# sFMC98_v2.net
KiCad netlist of a schematic drawn in Altium Designer
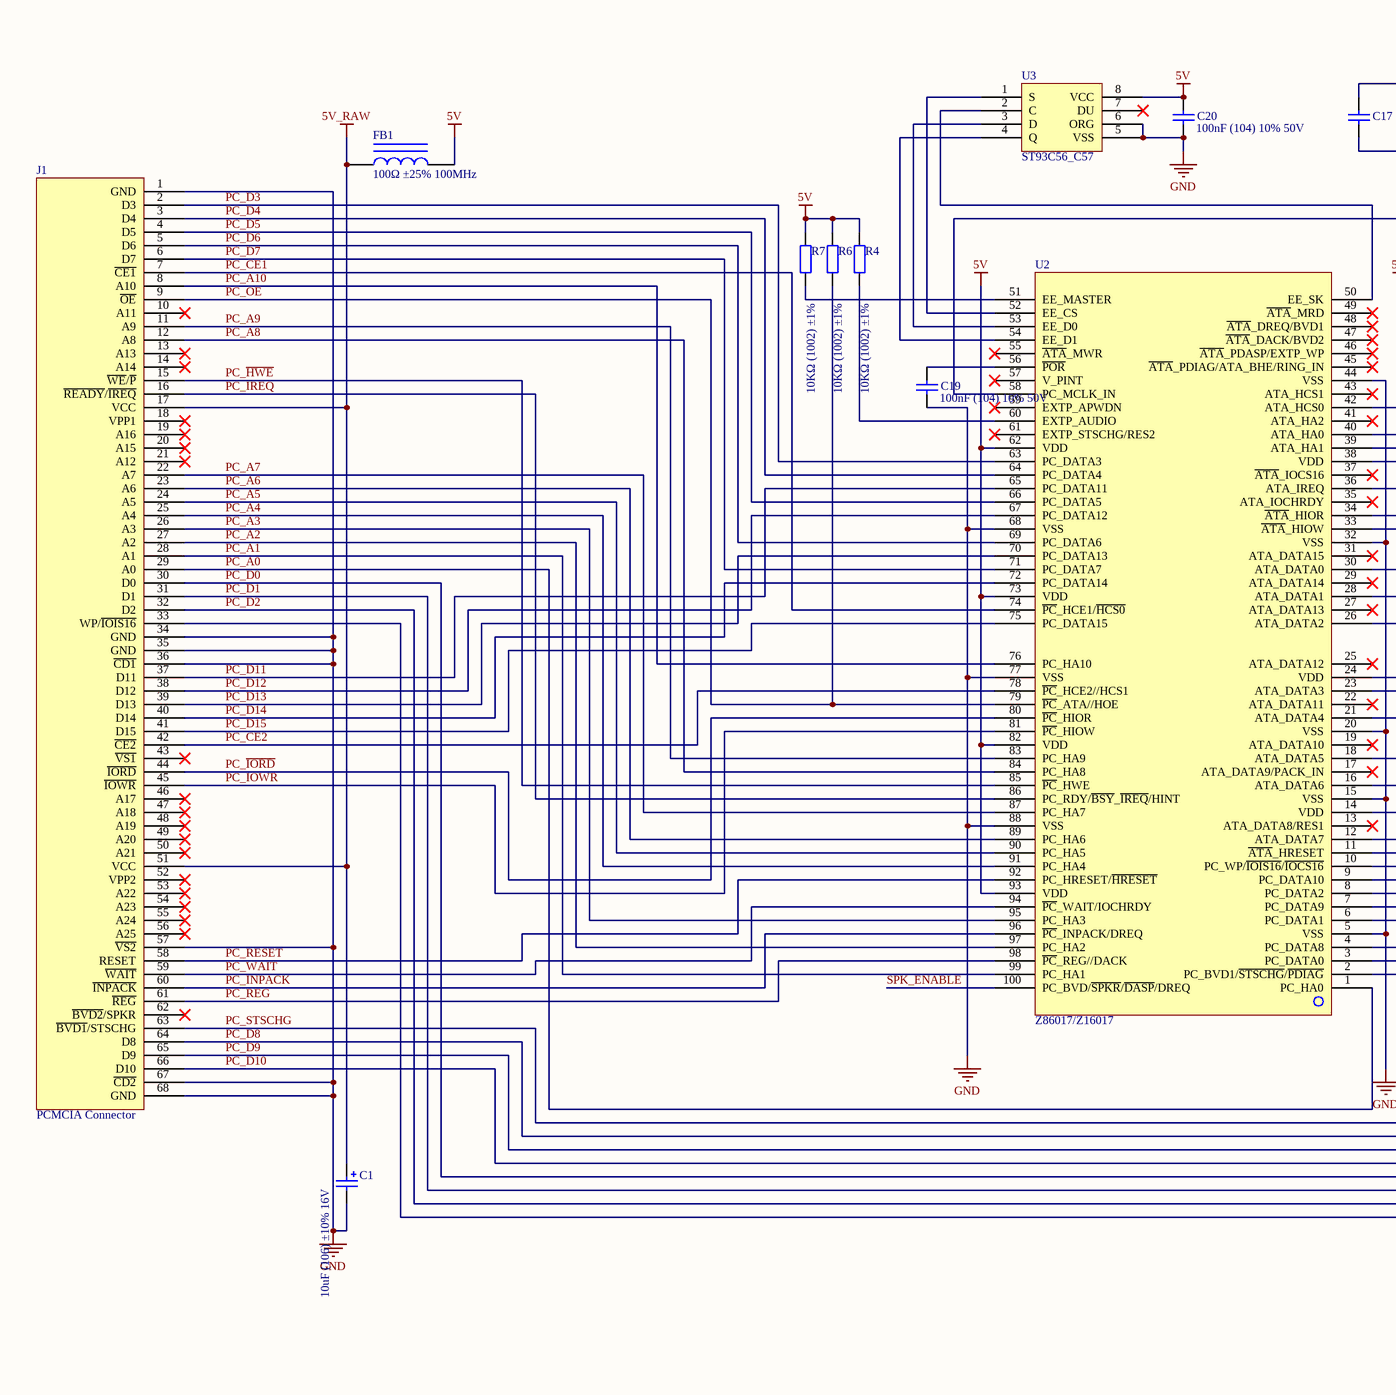
[diagram p0: sFMC98_v2.SchDoc, left]
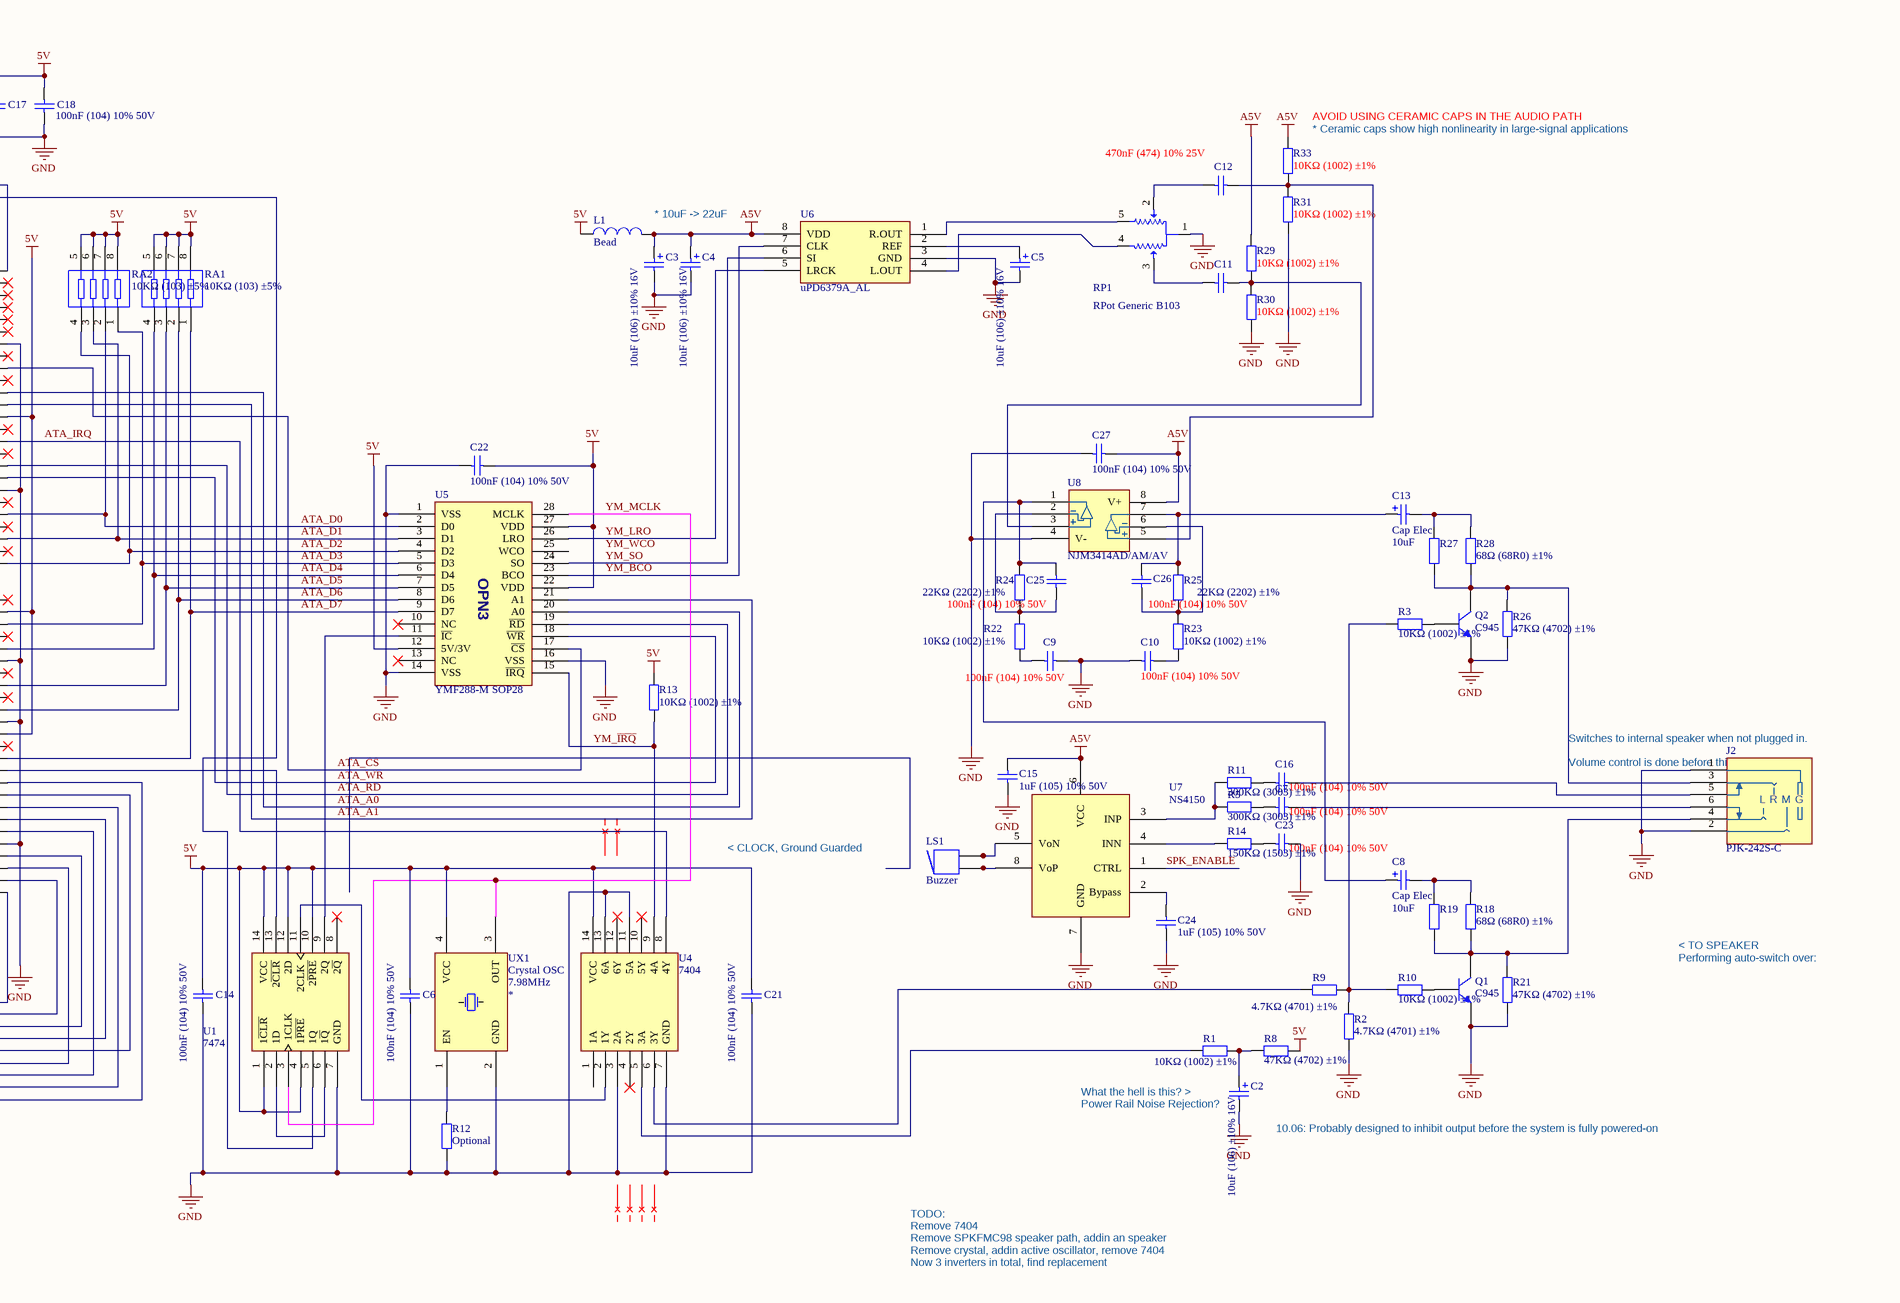
[diagram p1: sFMC98_v2.SchDoc, right]

(export (version "E")
  (design (tool "Eeschema 10.0.6"))
  (components
    (comp (ref "C1")
      (value "10uF (106) ±10% 16V")
      (footprint "CASE-A_3216")
      (description "钽电容")
      (libsource (lib "JLC_Cap") (part "3216 10uF (106) 10% 16V"))
    )
    (comp (ref "C2")
      (value "10uF (106) ±10% 16V")
      (footprint "CASE-A_3216")
      (description "钽电容")
      (libsource (lib "JLC_Cap") (part "3216 10uF (106) 10% 16V"))
    )
    (comp (ref "C3")
      (value "10uF (106) ±10% 16V")
      (footprint "CASE-A_3216")
      (description "钽电容")
      (libsource (lib "JLC_Cap") (part "3216 10uF (106) 10% 16V"))
    )
    (comp (ref "C4")
      (value "10uF (106) ±10% 16V")
      (footprint "CASE-A_3216")
      (description "钽电容")
      (libsource (lib "JLC_Cap") (part "3216 10uF (106) 10% 16V"))
    )
    (comp (ref "C5")
      (value "10uF (106) ±10% 16V")
      (footprint "CASE-A_3216")
      (description "钽电容")
      (libsource (lib "JLC_Cap") (part "3216 10uF (106) 10% 16V"))
    )
    (comp (ref "C6")
      (value "100nF (104) 10% 50V")
      (footprint "0603_C")
      (description "贴片电容")
      (libsource (lib "JLC_Cap") (part "0603 100nF (104) 10% 50V"))
    )
    (comp (ref "C7")
      (value "100nF (104) 10% 50V")
      (footprint "0603_C")
      (description "贴片电容")
      (libsource (lib "JLC_Cap") (part "0603 100nF (104) 10% 50V"))
    )
    (comp (ref "C8")
      (value "Cap Elec")
      (footprint "C-RB-4_5MM_Cutout")
      (description "Polarized Capacitor (Surface Mount)")
      (fields (field (name "ALTIUM_VALUE") "10uF") (field (name "PUBLISHER") "Altium Limited"))
      (libsource (lib "DiscreteRF") (part "Cap Pol3"))
    )
    (comp (ref "C9")
      (value "100nF (104) 10% 50V")
      (footprint "0603_C")
      (description "贴片电容")
      (libsource (lib "JLC_Cap") (part "0603 100nF (104) 10% 50V"))
    )
    (comp (ref "C10")
      (value "100nF (104) 10% 50V")
      (footprint "0603_C")
      (description "贴片电容")
      (libsource (lib "JLC_Cap") (part "0603 100nF (104) 10% 50V"))
    )
    (comp (ref "C11")
      (value "470nF (474) 10% 25V")
      (footprint "0603_C")
      (description "贴片电容")
      (libsource (lib "JLC_Cap") (part "0603 470nF (474) 10% 25V"))
    )
    (comp (ref "C12")
      (value "470nF (474) 10% 25V")
      (footprint "0603_C")
      (description "贴片电容")
      (libsource (lib "JLC_Cap") (part "0603 470nF (474) 10% 25V"))
    )
    (comp (ref "C13")
      (value "Cap Elec")
      (footprint "C-RB-4_5MM_Cutout")
      (description "Polarized Capacitor (Surface Mount)")
      (fields (field (name "ALTIUM_VALUE") "10uF") (field (name "PUBLISHER") "Altium Limited"))
      (libsource (lib "DiscreteRF") (part "Cap Pol3"))
    )
    (comp (ref "C14")
      (value "100nF (104) 10% 50V")
      (footprint "0603_C")
      (description "贴片电容")
      (libsource (lib "JLC_Cap") (part "0603 100nF (104) 10% 50V"))
    )
    (comp (ref "C15")
      (value "1uF (105) 10% 50V")
      (footprint "0603_C")
      (description "贴片电容")
      (libsource (lib "JLC_Cap") (part "0603 1uF (105) 10% 50V"))
    )
    (comp (ref "C16")
      (value "100nF (104) 10% 50V")
      (footprint "0603_C")
      (description "贴片电容")
      (libsource (lib "JLC_Cap") (part "0603 100nF (104) 10% 50V"))
    )
    (comp (ref "C17")
      (value "100nF (104) 10% 50V")
      (footprint "0603_C")
      (description "贴片电容")
      (libsource (lib "JLC_Cap") (part "0603 100nF (104) 10% 50V"))
    )
    (comp (ref "C18")
      (value "100nF (104) 10% 50V")
      (footprint "0603_C")
      (description "贴片电容")
      (libsource (lib "JLC_Cap") (part "0603 100nF (104) 10% 50V"))
    )
    (comp (ref "C19")
      (value "100nF (104) 10% 50V")
      (footprint "0603_C")
      (description "贴片电容")
      (libsource (lib "JLC_Cap") (part "0603 100nF (104) 10% 50V"))
    )
    (comp (ref "C20")
      (value "100nF (104) 10% 50V")
      (footprint "0603_C")
      (description "贴片电容")
      (libsource (lib "JLC_Cap") (part "0603 100nF (104) 10% 50V"))
    )
    (comp (ref "C21")
      (value "100nF (104) 10% 50V")
      (footprint "0603_C")
      (description "贴片电容")
      (libsource (lib "JLC_Cap") (part "0603 100nF (104) 10% 50V"))
    )
    (comp (ref "C22")
      (value "100nF (104) 10% 50V")
      (footprint "0603_C")
      (description "贴片电容")
      (libsource (lib "JLC_Cap") (part "0603 100nF (104) 10% 50V"))
    )
    (comp (ref "C23")
      (value "100nF (104) 10% 50V")
      (footprint "0603_C")
      (description "贴片电容")
      (libsource (lib "JLC_Cap") (part "0603 100nF (104) 10% 50V"))
    )
    (comp (ref "C24")
      (value "1uF (105) 10% 50V")
      (footprint "0603_C")
      (description "贴片电容")
      (libsource (lib "JLC_Cap") (part "0603 1uF (105) 10% 50V"))
    )
    (comp (ref "C25")
      (value "100nF (104) 10% 50V")
      (footprint "0603_C")
      (description "贴片电容")
      (libsource (lib "JLC_Cap") (part "0603 100nF (104) 10% 50V"))
    )
    (comp (ref "C26")
      (value "100nF (104) 10% 50V")
      (footprint "0603_C")
      (description "贴片电容")
      (libsource (lib "JLC_Cap") (part "0603 100nF (104) 10% 50V"))
    )
    (comp (ref "C27")
      (value "100nF (104) 10% 50V")
      (footprint "0603_C")
      (description "贴片电容")
      (libsource (lib "JLC_Cap") (part "0603 100nF (104) 10% 50V"))
    )
    (comp (ref "FB1")
      (value "100Ω ±25% 100MHz")
      (footprint "0805_L")
      (description "贴片磁珠")
      (libsource (lib "JLC_IUD") (part "0805 100Ω 25% 100MHz"))
    )
    (comp (ref "J1")
      (value "PCMCIA Connector")
      (footprint "PCF-SMT-K1")
      (libsource (lib "PrimaryLIB1") (part "PCMCIA_Conn"))
    )
    (comp (ref "J2")
      (value "PJK-242S-C")
      (footprint "PJK-242S-C")
      (description "2.5mm Headphone Jack")
      (libsource (lib "PrimaryLIB1") (part "PJK-242S-C"))
    )
    (comp (ref "L1")
      (value "Bead")
      (footprint "L2012X10N_LQW21")
      (description "Inductor")
      (fields (field (name "PUBLISHER") "Altium Limited"))
      (libsource (lib "DiscreteRF") (part "Inductor"))
    )
    (comp (ref "LS1")
      (value "Buzzer")
      (footprint "SPK_PCB_MOUNT")
      (description "Magnetic Transducer Buzzer")
      (fields (field (name "PUBLISHER") "Altium Limited"))
      (libsource (lib "Miscellaneous Devices") (part "Buzzer"))
    )
    (comp (ref "Q1")
      (value "C945")
      (footprint "SOT-23(SOT-23-3)")
      (description "三极管")
      (libsource (lib "JLC_Transistor_NPN") (part "SOT-23 SS8050 Y1"))
    )
    (comp (ref "Q2")
      (value "C945")
      (footprint "SOT-23(SOT-23-3)")
      (description "三极管")
      (libsource (lib "JLC_Transistor_NPN") (part "SOT-23 SS8050 Y1"))
    )
    (comp (ref "R1")
      (value "10KΩ (1002) ±1%")
      (footprint "0603_R")
      (description "贴片电阻")
      (libsource (lib "") (part "0603 10KΩ (1002) 1%_1"))
    )
    (comp (ref "R2")
      (value "4.7KΩ (4701) ±1%")
      (footprint "0603_R")
      (description "贴片电阻")
      (libsource (lib "") (part "0603 4.7KΩ (4701) 1%_1"))
    )
    (comp (ref "R3")
      (value "10KΩ (1002) ±1%")
      (footprint "0603_R")
      (description "贴片电阻")
      (libsource (lib "") (part "0603 10KΩ (1002) 1%_1"))
    )
    (comp (ref "R4")
      (value "10KΩ (1002) ±1%")
      (footprint "0603_R")
      (description "贴片电阻")
      (libsource (lib "JLC_RES") (part "0603 10KΩ (1002) 1%"))
    )
    (comp (ref "R5")
      (value "300KΩ (3003) ±1%")
      (footprint "0603_R")
      (description "贴片电阻")
      (libsource (lib "JLC_RES") (part "0603 300KΩ (3003) 1%"))
    )
    (comp (ref "R6")
      (value "10KΩ (1002) ±1%")
      (footprint "0603_R")
      (description "贴片电阻")
      (libsource (lib "JLC_RES") (part "0603 10KΩ (1002) 1%"))
    )
    (comp (ref "R7")
      (value "10KΩ (1002) ±1%")
      (footprint "0603_R")
      (description "贴片电阻")
      (libsource (lib "JLC_RES") (part "0603 10KΩ (1002) 1%"))
    )
    (comp (ref "R8")
      (value "47KΩ (4702) ±1%")
      (footprint "0603_R")
      (description "贴片电阻")
      (libsource (lib "") (part "0603 47KΩ (4702) 1%_1"))
    )
    (comp (ref "R9")
      (value "4.7KΩ (4701) ±1%")
      (footprint "0603_R")
      (description "贴片电阻")
      (libsource (lib "JLC_RES") (part "0603 4.7KΩ (4701) 1%"))
    )
    (comp (ref "R10")
      (value "10KΩ (1002) ±1%")
      (footprint "0603_R")
      (description "贴片电阻")
      (libsource (lib "") (part "0603 10KΩ (1002) 1%_1"))
    )
    (comp (ref "R11")
      (value "300KΩ (3003) ±1%")
      (footprint "0603_R")
      (description "贴片电阻")
      (libsource (lib "JLC_RES") (part "0603 300KΩ (3003) 1%"))
    )
    (comp (ref "R12")
      (value "Optional")
      (footprint "0603_R")
      (description "贴片电阻")
      (libsource (lib "JLC_RES") (part "0603 10KΩ (1002) 1%"))
    )
    (comp (ref "R13")
      (value "10KΩ (1002) ±1%")
      (footprint "0603_R")
      (description "贴片电阻")
      (libsource (lib "JLC_RES") (part "0603 10KΩ (1002) 1%"))
    )
    (comp (ref "R14")
      (value "150KΩ (1503) ±1%")
      (footprint "0603_R")
      (description "贴片电阻")
      (libsource (lib "JLC_RES") (part "0603 150KΩ (1503) 1%"))
    )
    (comp (ref "R18")
      (value "68Ω (68R0) ±1%")
      (footprint "0603_R")
      (description "贴片电阻")
      (libsource (lib "JLC_RES") (part "0603 68Ω (68R0) 1%"))
    )
    (comp (ref "R19")
      (value "68Ω (68R0) ±1%")
      (footprint "0603_R")
      (description "贴片电阻")
      (libsource (lib "JLC_RES") (part "0603 68Ω (68R0) 1%"))
    )
    (comp (ref "R21")
      (value "47KΩ (4702) ±1%")
      (footprint "0603_R")
      (description "贴片电阻")
      (libsource (lib "JLC_RES") (part "0603 47KΩ (4702) 1%"))
    )
    (comp (ref "R22")
      (value "10KΩ (1002) ±1%")
      (footprint "0603_R")
      (description "贴片电阻")
      (libsource (lib "JLC_RES") (part "0603 10KΩ (1002) 1%"))
    )
    (comp (ref "R23")
      (value "10KΩ (1002) ±1%")
      (footprint "0603_R")
      (description "贴片电阻")
      (libsource (lib "JLC_RES") (part "0603 10KΩ (1002) 1%"))
    )
    (comp (ref "R24")
      (value "22KΩ (2202) ±1%")
      (footprint "0603_R")
      (description "贴片电阻")
      (libsource (lib "JLC_RES") (part "0603 22KΩ (2202) 1%"))
    )
    (comp (ref "R25")
      (value "22KΩ (2202) ±1%")
      (footprint "0603_R")
      (description "贴片电阻")
      (libsource (lib "JLC_RES") (part "0603 22KΩ (2202) 1%"))
    )
    (comp (ref "R26")
      (value "47KΩ (4702) ±1%")
      (footprint "0603_R")
      (description "贴片电阻")
      (libsource (lib "JLC_RES") (part "0603 47KΩ (4702) 1%"))
    )
    (comp (ref "R27")
      (value "68Ω (68R0) ±1%")
      (footprint "0603_R")
      (description "贴片电阻")
      (libsource (lib "JLC_RES") (part "0603 68Ω (68R0) 1%"))
    )
    (comp (ref "R28")
      (value "68Ω (68R0) ±1%")
      (footprint "0603_R")
      (description "贴片电阻")
      (libsource (lib "JLC_RES") (part "0603 68Ω (68R0) 1%"))
    )
    (comp (ref "R29")
      (value "10KΩ (1002) ±1%")
      (footprint "0603_R")
      (description "贴片电阻")
      (libsource (lib "JLC_RES") (part "0603 10KΩ (1002) 1%"))
    )
    (comp (ref "R30")
      (value "10KΩ (1002) ±1%")
      (footprint "0603_R")
      (description "贴片电阻")
      (libsource (lib "JLC_RES") (part "0603 10KΩ (1002) 1%"))
    )
    (comp (ref "R31")
      (value "10KΩ (1002) ±1%")
      (footprint "0603_R")
      (description "贴片电阻")
      (libsource (lib "JLC_RES") (part "0603 10KΩ (1002) 1%"))
    )
    (comp (ref "R33")
      (value "10KΩ (1002) ±1%")
      (footprint "0603_R")
      (description "贴片电阻")
      (libsource (lib "JLC_RES") (part "0603 10KΩ (1002) 1%"))
    )
    (comp (ref "RA1")
      (value "10KΩ (103) ±5%")
      (footprint "0603_Rx4")
      (description "贴片排阻")
      (libsource (lib "JLC_RES") (part "0603*4  10KΩ (103) 5%"))
    )
    (comp (ref "RA2")
      (value "10KΩ (103) ±5%")
      (footprint "0603_Rx4")
      (description "贴片排阻")
      (libsource (lib "JLC_RES") (part "0603*4  10KΩ (103) 5%"))
    )
    (comp (ref "RP1")
      (value "RPot Generic B103")
      (footprint "RPot_RK10J12E_ALPS")
      (libsource (lib "PrimaryLIB1") (part "RPot_Generic_Bxxx"))
    )
    (comp (ref "U1")
      (value "7474")
      (footprint "TSSOP14_TSOP65P640X120-14N")
      (description "Dual D-Type Positive-Edge-Triggered Flip-Flops With Preset And Clear")
      (libsource (lib "7400") (part "7474_J_N_1"))
    )
    (comp (ref "U2")
      (value "Z86017/Z16017")
      (footprint "VQFP100_TSQFP50P1600X1600X160-100N")
      (libsource (lib "PrimaryLIB1") (part "ZX6017"))
    )
    (comp (ref "U3")
      (value "ST93C56_C57")
      (footprint "SOIC-8 NB")
      (description "2K (128 x 16 or 256 x 8) SERIAL MICROWIRE EEPROM")
      (libsource (lib "PrimaryLIB1") (part "ST93C56_C57"))
    )
    (comp (ref "U4")
      (value "7404")
      (footprint "TSSOP14_TSOP65P640X120-14N")
      (description "Hex Inverter")
      (libsource (lib "7400") (part "7404_J_N_1"))
    )
    (comp (ref "U5")
      (value "YMF288-M SOP28")
      (footprint "SOP127P1030X265-28N")
      (libsource (lib "Audio") (part "YMF288_M"))
    )
    (comp (ref "U6")
      (value "uPD6379A_AL")
      (footprint "DMP8_SOIC127P680X175-8N")
      (description "2-CHANNEL 16-BIT D/A CONVERTER FOR AUDIO APPLICATION")
      (libsource (lib "Audio") (part "uPD6379A_AL"))
    )
    (comp (ref "U7")
      (value "NS4150")
      (footprint "MS8")
      (description "超低 EMI、无需滤波器、3W 单声道 D 类音频功放")
      (libsource (lib "PrimaryLIB1") (part "NS4150"))
    )
    (comp (ref "U8")
      (value "NJM3414AD/AM/AV")
      (footprint "DMP8_SOIC127P680X175-8N")
      (description "Single-Supply Dual High Current Operational Amplifier")
      (libsource (lib "PrimaryLIB1") (part "NJM3414AD_AM_AV_1"))
    )
    (comp (ref "UX1")
      (value "Crystal OSC")
      (footprint "SMD-3225_4P")
      (fields (field (name "FREQ") "7.98MHz") (field (name "TYPE") "*"))
      (libsource (lib "PrimaryLIB1") (part "XTAL_OSC"))
    )
  )
  (nets
    (net (code "1") (name "/ATA_A0") (class "Default")
      (node (ref "U2") (pin "40") (pinfunction "ATA_HA0_40") (pintype "passive"))
      (node (ref "U5") (pin "20") (pinfunction "A0_20") (pintype "passive"))
    )
    (net (code "2") (name "/ATA_A1") (class "Default")
      (node (ref "U2") (pin "39") (pinfunction "ATA_HA1_39") (pintype "passive"))
      (node (ref "U5") (pin "21") (pinfunction "A1_21") (pintype "passive"))
    )
    (net (code "3") (name "/ATA_D0") (class "Default")
      (node (ref "RA2") (pin "2") (pinfunction "2_2") (pintype "passive"))
      (node (ref "U2") (pin "30") (pinfunction "ATA_DATA0_30") (pintype "passive"))
      (node (ref "U5") (pin "2") (pinfunction "D0_2") (pintype "passive"))
    )
    (net (code "4") (name "/ATA_D1") (class "Default")
      (node (ref "RA2") (pin "3") (pinfunction "3_3") (pintype "passive"))
      (node (ref "U2") (pin "28") (pinfunction "ATA_DATA1_28") (pintype "passive"))
      (node (ref "U5") (pin "3") (pinfunction "D1_3") (pintype "passive"))
    )
    (net (code "5") (name "/ATA_D2") (class "Default")
      (node (ref "RA2") (pin "4") (pinfunction "4_4") (pintype "passive"))
      (node (ref "U2") (pin "26") (pinfunction "ATA_DATA2_26") (pintype "passive"))
      (node (ref "U5") (pin "4") (pinfunction "D2_4") (pintype "passive"))
    )
    (net (code "6") (name "/ATA_D3") (class "Default")
      (node (ref "RA2") (pin "1") (pinfunction "1_1") (pintype "passive"))
      (node (ref "U2") (pin "23") (pinfunction "ATA_DATA3_23") (pintype "passive"))
      (node (ref "U5") (pin "5") (pinfunction "D3_5") (pintype "passive"))
    )
    (net (code "7") (name "/ATA_D4") (class "Default")
      (node (ref "RA1") (pin "4") (pinfunction "4_4") (pintype "passive"))
      (node (ref "U2") (pin "21") (pinfunction "ATA_DATA4_21") (pintype "passive"))
      (node (ref "U5") (pin "6") (pinfunction "D4_6") (pintype "passive"))
    )
    (net (code "8") (name "/ATA_D5") (class "Default")
      (node (ref "RA1") (pin "3") (pinfunction "3_3") (pintype "passive"))
      (node (ref "U2") (pin "18") (pinfunction "ATA_DATA5_18") (pintype "passive"))
      (node (ref "U5") (pin "7") (pinfunction "D5_7") (pintype "passive"))
    )
    (net (code "9") (name "/ATA_D6") (class "Default")
      (node (ref "RA1") (pin "2") (pinfunction "2_2") (pintype "passive"))
      (node (ref "U2") (pin "16") (pinfunction "ATA_DATA6_16") (pintype "passive"))
      (node (ref "U5") (pin "8") (pinfunction "D6_8") (pintype "passive"))
    )
    (net (code "10") (name "/ATA_D7") (class "Default")
      (node (ref "RA1") (pin "1") (pinfunction "1_1") (pintype "passive"))
      (node (ref "U2") (pin "12") (pinfunction "ATA_DATA7_12") (pintype "passive"))
      (node (ref "U5") (pin "9") (pinfunction "D7_9") (pintype "passive"))
    )
    (net (code "11") (name "/ATA_IRQ") (class "Default")
      (node (ref "U2") (pin "36") (pinfunction "ATA_IREQ_36") (pintype "passive"))
      (node (ref "U4") (pin "8") (pinfunction "4Y_8") (pintype "passive"))
    )
    (net (code "12") (name "/ATA_~{CS}") (class "Default")
      (node (ref "U2") (pin "42") (pinfunction "ATA_HCS0_42") (pintype "passive"))
      (node (ref "U5") (pin "17") (pinfunction "~{CS}_17") (pintype "passive"))
    )
    (net (code "13") (name "/ATA_~{RD}") (class "Default")
      (node (ref "U2") (pin "34") (pinfunction "~{ATA}_HIOR_34") (pintype "passive"))
      (node (ref "U5") (pin "19") (pinfunction "~{RD}_19") (pintype "passive"))
    )
    (net (code "14") (name "/ATA_~{WR}") (class "Default")
      (node (ref "U2") (pin "33") (pinfunction "~{ATA}_HIOW_33") (pintype "passive"))
      (node (ref "U5") (pin "18") (pinfunction "~{WR}_18") (pintype "passive"))
    )
    (net (code "15") (name "/PC_A0") (class "Default")
      (node (ref "J1") (pin "29") (pinfunction "A0_29") (pintype "passive"))
      (node (ref "U2") (pin "1") (pinfunction "PC_HA0_1") (pintype "passive"))
    )
    (net (code "16") (name "/PC_A1") (class "Default")
      (node (ref "J1") (pin "28") (pinfunction "A1_28") (pintype "passive"))
      (node (ref "U2") (pin "99") (pinfunction "PC_HA1_99") (pintype "passive"))
    )
    (net (code "17") (name "/PC_A2") (class "Default")
      (node (ref "J1") (pin "27") (pinfunction "A2_27") (pintype "passive"))
      (node (ref "U2") (pin "97") (pinfunction "PC_HA2_97") (pintype "passive"))
    )
    (net (code "18") (name "/PC_A3") (class "Default")
      (node (ref "J1") (pin "26") (pinfunction "A3_26") (pintype "passive"))
      (node (ref "U2") (pin "95") (pinfunction "PC_HA3_95") (pintype "passive"))
    )
    (net (code "19") (name "/PC_A4") (class "Default")
      (node (ref "J1") (pin "25") (pinfunction "A4_25") (pintype "passive"))
      (node (ref "U2") (pin "91") (pinfunction "PC_HA4_91") (pintype "passive"))
    )
    (net (code "20") (name "/PC_A5") (class "Default")
      (node (ref "J1") (pin "24") (pinfunction "A5_24") (pintype "passive"))
      (node (ref "U2") (pin "90") (pinfunction "PC_HA5_90") (pintype "passive"))
    )
    (net (code "21") (name "/PC_A6") (class "Default")
      (node (ref "J1") (pin "23") (pinfunction "A6_23") (pintype "passive"))
      (node (ref "U2") (pin "89") (pinfunction "PC_HA6_89") (pintype "passive"))
    )
    (net (code "22") (name "/PC_A7") (class "Default")
      (node (ref "J1") (pin "22") (pinfunction "A7_22") (pintype "passive"))
      (node (ref "U2") (pin "87") (pinfunction "PC_HA7_87") (pintype "passive"))
    )
    (net (code "23") (name "/PC_A8") (class "Default")
      (node (ref "J1") (pin "12") (pinfunction "A8_12") (pintype "passive"))
      (node (ref "U2") (pin "84") (pinfunction "PC_HA8_84") (pintype "passive"))
    )
    (net (code "24") (name "/PC_A9") (class "Default")
      (node (ref "J1") (pin "11") (pinfunction "A9_11") (pintype "passive"))
      (node (ref "U2") (pin "83") (pinfunction "PC_HA9_83") (pintype "passive"))
    )
    (net (code "25") (name "/PC_A10") (class "Default")
      (node (ref "J1") (pin "8") (pinfunction "A10_8") (pintype "passive"))
      (node (ref "U2") (pin "76") (pinfunction "PC_HA10_76") (pintype "passive"))
    )
    (net (code "26") (name "/PC_D0") (class "Default")
      (node (ref "J1") (pin "30") (pinfunction "D0_30") (pintype "passive"))
      (node (ref "U2") (pin "3") (pinfunction "PC_DATA0_3") (pintype "passive"))
    )
    (net (code "27") (name "/PC_D1") (class "Default")
      (node (ref "J1") (pin "31") (pinfunction "D1_31") (pintype "passive"))
      (node (ref "U2") (pin "6") (pinfunction "PC_DATA1_6") (pintype "passive"))
    )
    (net (code "28") (name "/PC_D2") (class "Default")
      (node (ref "J1") (pin "32") (pinfunction "D2_32") (pintype "passive"))
      (node (ref "U2") (pin "8") (pinfunction "PC_DATA2_8") (pintype "passive"))
    )
    (net (code "29") (name "/PC_D3") (class "Default")
      (node (ref "J1") (pin "2") (pinfunction "D3_2") (pintype "passive"))
      (node (ref "U2") (pin "63") (pinfunction "PC_DATA3_63") (pintype "passive"))
    )
    (net (code "30") (name "/PC_D4") (class "Default")
      (node (ref "J1") (pin "3") (pinfunction "D4_3") (pintype "passive"))
      (node (ref "U2") (pin "64") (pinfunction "PC_DATA4_64") (pintype "passive"))
    )
    (net (code "31") (name "/PC_D5") (class "Default")
      (node (ref "J1") (pin "4") (pinfunction "D5_4") (pintype "passive"))
      (node (ref "U2") (pin "66") (pinfunction "PC_DATA5_66") (pintype "passive"))
    )
    (net (code "32") (name "/PC_D6") (class "Default")
      (node (ref "J1") (pin "5") (pinfunction "D6_5") (pintype "passive"))
      (node (ref "U2") (pin "69") (pinfunction "PC_DATA6_69") (pintype "passive"))
    )
    (net (code "33") (name "/PC_D7") (class "Default")
      (node (ref "J1") (pin "6") (pinfunction "D7_6") (pintype "passive"))
      (node (ref "U2") (pin "71") (pinfunction "PC_DATA7_71") (pintype "passive"))
    )
    (net (code "34") (name "/PC_D8") (class "Default")
      (node (ref "J1") (pin "64") (pinfunction "D8_64") (pintype "passive"))
      (node (ref "U2") (pin "4") (pinfunction "PC_DATA8_4") (pintype "passive"))
    )
    (net (code "35") (name "/PC_D9") (class "Default")
      (node (ref "J1") (pin "65") (pinfunction "D9_65") (pintype "passive"))
      (node (ref "U2") (pin "7") (pinfunction "PC_DATA9_7") (pintype "passive"))
    )
    (net (code "36") (name "/PC_D10") (class "Default")
      (node (ref "J1") (pin "66") (pinfunction "D10_66") (pintype "passive"))
      (node (ref "U2") (pin "9") (pinfunction "PC_DATA10_9") (pintype "passive"))
    )
    (net (code "37") (name "/PC_D11") (class "Default")
      (node (ref "J1") (pin "37") (pinfunction "D11_37") (pintype "passive"))
      (node (ref "U2") (pin "65") (pinfunction "PC_DATA11_65") (pintype "passive"))
    )
    (net (code "38") (name "/PC_D12") (class "Default")
      (node (ref "J1") (pin "38") (pinfunction "D12_38") (pintype "passive"))
      (node (ref "U2") (pin "67") (pinfunction "PC_DATA12_67") (pintype "passive"))
    )
    (net (code "39") (name "/PC_D13") (class "Default")
      (node (ref "J1") (pin "39") (pinfunction "D13_39") (pintype "passive"))
      (node (ref "U2") (pin "70") (pinfunction "PC_DATA13_70") (pintype "passive"))
    )
    (net (code "40") (name "/PC_D14") (class "Default")
      (node (ref "J1") (pin "40") (pinfunction "D14_40") (pintype "passive"))
      (node (ref "U2") (pin "72") (pinfunction "PC_DATA14_72") (pintype "passive"))
    )
    (net (code "41") (name "/PC_D15") (class "Default")
      (node (ref "J1") (pin "41") (pinfunction "D15_41") (pintype "passive"))
      (node (ref "U2") (pin "75") (pinfunction "PC_DATA15_75") (pintype "passive"))
    )
    (net (code "42") (name "/PC_RESET") (class "Default")
      (node (ref "J1") (pin "58") (pinfunction "RESET_58") (pintype "passive"))
      (node (ref "U2") (pin "92") (pinfunction "PC_HRESET/~{HRESET}_92") (pintype "passive"))
    )
    (net (code "43") (name "/PC_STSCHG") (class "Default")
      (node (ref "J1") (pin "63") (pinfunction "~{BVD1}/STSCHG_63") (pintype "passive"))
      (node (ref "U2") (pin "2") (pinfunction "PC_BVD1/~{STSCHG}/~{PDIAG}_2") (pintype "passive"))
    )
    (net (code "44") (name "/PC_~{CE1}") (class "Default")
      (node (ref "J1") (pin "7") (pinfunction "~{CE1}_7") (pintype "passive"))
      (node (ref "U2") (pin "74") (pinfunction "~{PC}_HCE1/~{HCS0}_74") (pintype "passive"))
    )
    (net (code "45") (name "/PC_~{CE2}") (class "Default")
      (node (ref "J1") (pin "42") (pinfunction "~{CE2}_42") (pintype "passive"))
      (node (ref "U2") (pin "78") (pinfunction "~{PC}_HCE2//HCS1_78") (pintype "passive"))
    )
    (net (code "46") (name "/PC_~{HWE}") (class "Default")
      (node (ref "J1") (pin "15") (pinfunction "~{WE}/~{P}_15") (pintype "passive"))
      (node (ref "U2") (pin "85") (pinfunction "~{PC}_HWE_85") (pintype "passive"))
    )
    (net (code "47") (name "/PC_~{INPACK}") (class "Default")
      (node (ref "J1") (pin "60") (pinfunction "~{INPACK}_60") (pintype "passive"))
      (node (ref "U2") (pin "96") (pinfunction "~{PC}_INPACK/DREQ_96") (pintype "passive"))
    )
    (net (code "48") (name "/PC_~{IORD}") (class "Default")
      (node (ref "J1") (pin "44") (pinfunction "~{IORD}_44") (pintype "passive"))
      (node (ref "U2") (pin "80") (pinfunction "~{PC}_HIOR_80") (pintype "passive"))
    )
    (net (code "49") (name "/PC_~{IOWR}") (class "Default")
      (node (ref "J1") (pin "45") (pinfunction "~{IOWR}_45") (pintype "passive"))
      (node (ref "U2") (pin "81") (pinfunction "~{PC}_HIOW_81") (pintype "passive"))
    )
    (net (code "50") (name "/PC_~{IREQ}") (class "Default")
      (node (ref "J1") (pin "16") (pinfunction "~{READY}/~{IREQ}_16") (pintype "passive"))
      (node (ref "U2") (pin "86") (pinfunction "PC_RDY/~{BSY}_~{IREQ}/HINT_86") (pintype "passive"))
    )
    (net (code "51") (name "/PC_~{OE}") (class "Default")
      (node (ref "J1") (pin "9") (pinfunction "~{OE}_9") (pintype "passive"))
      (node (ref "R6") (pin "1") (pinfunction "1_1") (pintype "passive"))
      (node (ref "U2") (pin "79") (pinfunction "~{PC}_ATA//HOE_79") (pintype "passive"))
    )
    (net (code "52") (name "/PC_~{REG}") (class "Default")
      (node (ref "J1") (pin "61") (pinfunction "~{REG}_61") (pintype "passive"))
      (node (ref "U2") (pin "98") (pinfunction "~{PC}_REG//DACK_98") (pintype "passive"))
    )
    (net (code "53") (name "/PC_~{WAIT}") (class "Default")
      (node (ref "J1") (pin "59") (pinfunction "~{WAIT}_59") (pintype "passive"))
      (node (ref "U2") (pin "94") (pinfunction "~{PC}_WAIT/IOCHRDY_94") (pintype "passive"))
    )
    (net (code "54") (name "/SPK_ENABLE") (class "Default")
      (node (ref "U2") (pin "100") (pinfunction "PC_BVD/~{SPKR}/~{DASP}/DREQ_100") (pintype "passive"))
      (node (ref "U7") (pin "1") (pinfunction "CTRL_1") (pintype "passive"))
    )
    (net (code "55") (name "/YM_BCO") (class "Default")
      (node (ref "U5") (pin "23") (pinfunction "BCO_23") (pintype "passive"))
      (node (ref "U6") (pin "7") (pinfunction "CLK_7") (pintype "passive"))
    )
    (net (code "56") (name "/YM_LRO") (class "Default")
      (node (ref "U5") (pin "26") (pinfunction "LRO_26") (pintype "passive"))
      (node (ref "U6") (pin "5") (pinfunction "LRCK_5") (pintype "passive"))
    )
    (net (code "57") (name "/YM_MCLK") (class "Default")
      (node (ref "U1") (pin "3") (pinfunction "1CLK_3") (pintype "passive"))
      (node (ref "U5") (pin "28") (pinfunction "MCLK_28") (pintype "passive"))
      (node (ref "UX1") (pin "3") (pinfunction "OUT_3") (pintype "passive"))
    )
    (net (code "58") (name "/YM_SO") (class "Default")
      (node (ref "U5") (pin "24") (pinfunction "SO_24") (pintype "passive"))
      (node (ref "U6") (pin "6") (pinfunction "SI_6") (pintype "passive"))
    )
    (net (code "60") (name "/YM_~{IRQ}") (class "Default")
      (node (ref "R13") (pin "1") (pinfunction "1_1") (pintype "passive"))
      (node (ref "U4") (pin "9") (pinfunction "4A_9") (pintype "passive"))
      (node (ref "U5") (pin "15") (pinfunction "~{IRQ}_15") (pintype "passive"))
    )
    (net (code "61") (name "5V") (class "Default")
      (node (ref "C14") (pin "2") (pinfunction "2_2") (pintype "passive"))
      (node (ref "C17") (pin "2") (pinfunction "2_2") (pintype "passive"))
      (node (ref "C18") (pin "2") (pinfunction "2_2") (pintype "passive"))
      (node (ref "C20") (pin "2") (pinfunction "2_2") (pintype "passive"))
      (node (ref "C21") (pin "2") (pinfunction "2_2") (pintype "passive"))
      (node (ref "C22") (pin "1") (pinfunction "1_1") (pintype "passive"))
      (node (ref "C6") (pin "2") (pinfunction "2_2") (pintype "passive"))
      (node (ref "FB1") (pin "2") (pinfunction "2_2") (pintype "passive"))
      (node (ref "L1") (pin "2") (pinfunction "2_2") (pintype "passive"))
      (node (ref "R13") (pin "2") (pinfunction "2_2") (pintype "passive"))
      (node (ref "R4") (pin "2") (pinfunction "2_2") (pintype "passive"))
      (node (ref "R6") (pin "2") (pinfunction "2_2") (pintype "passive"))
      (node (ref "R7") (pin "2") (pinfunction "2_2") (pintype "passive"))
      (node (ref "R8") (pin "1") (pinfunction "1_1") (pintype "passive"))
      (node (ref "RA1") (pin "5") (pinfunction "5_5") (pintype "passive"))
      (node (ref "RA1") (pin "6") (pinfunction "6_6") (pintype "passive"))
      (node (ref "RA1") (pin "7") (pinfunction "7_7") (pintype "passive"))
      (node (ref "RA1") (pin "8") (pinfunction "8_8") (pintype "passive"))
      (node (ref "RA2") (pin "5") (pinfunction "5_5") (pintype "passive"))
      (node (ref "RA2") (pin "6") (pinfunction "6_6") (pintype "passive"))
      (node (ref "RA2") (pin "7") (pinfunction "7_7") (pintype "passive"))
      (node (ref "RA2") (pin "8") (pinfunction "8_8") (pintype "passive"))
      (node (ref "U1") (pin "1") (pinfunction "1~{CLR}_1") (pintype "passive"))
      (node (ref "U1") (pin "10") (pinfunction "2~{PRE}_10") (pintype "passive"))
      (node (ref "U1") (pin "12") (pinfunction "2D_12") (pintype "passive"))
      (node (ref "U1") (pin "14") (pinfunction "VCC_14") (pintype "passive"))
      (node (ref "U1") (pin "4") (pinfunction "1~{PRE}_4") (pintype "passive"))
      (node (ref "U2") (pin "14") (pinfunction "VDD_14") (pintype "passive"))
      (node (ref "U2") (pin "24") (pinfunction "VDD_24") (pintype "passive"))
      (node (ref "U2") (pin "38") (pinfunction "VDD_38") (pintype "passive"))
      (node (ref "U2") (pin "62") (pinfunction "VDD_62") (pintype "passive"))
      (node (ref "U2") (pin "73") (pinfunction "VDD_73") (pintype "passive"))
      (node (ref "U2") (pin "82") (pinfunction "VDD_82") (pintype "passive"))
      (node (ref "U2") (pin "93") (pinfunction "VDD_93") (pintype "passive"))
      (node (ref "U3") (pin "8") (pinfunction "VCC_8") (pintype "passive"))
      (node (ref "U4") (pin "14") (pinfunction "VCC_14") (pintype "passive"))
      (node (ref "U5") (pin "12") (pinfunction "5V/3V_12") (pintype "passive"))
      (node (ref "U5") (pin "22") (pinfunction "VDD_22") (pintype "passive"))
      (node (ref "U5") (pin "27") (pinfunction "VDD_27") (pintype "passive"))
      (node (ref "UX1") (pin "4") (pinfunction "VCC_4") (pintype "passive"))
    )
    (net (code "62") (name "5V_RAW") (class "Default")
      (node (ref "C1") (pin "1") (pinfunction "1_1") (pintype "passive"))
      (node (ref "FB1") (pin "1") (pinfunction "1_1") (pintype "passive"))
      (node (ref "J1") (pin "17") (pinfunction "VCC_17") (pintype "passive"))
      (node (ref "J1") (pin "51") (pinfunction "VCC_51") (pintype "passive"))
    )
    (net (code "63") (name "A5V") (class "Default")
      (node (ref "C15") (pin "2") (pinfunction "2_2") (pintype "passive"))
      (node (ref "C27") (pin "1") (pinfunction "1_1") (pintype "passive"))
      (node (ref "C3") (pin "1") (pinfunction "1_1") (pintype "passive"))
      (node (ref "C4") (pin "1") (pinfunction "1_1") (pintype "passive"))
      (node (ref "L1") (pin "1") (pinfunction "1_1") (pintype "passive"))
      (node (ref "R29") (pin "2") (pinfunction "2_2") (pintype "passive"))
      (node (ref "R33") (pin "2") (pinfunction "2_2") (pintype "passive"))
      (node (ref "U6") (pin "8") (pinfunction "VDD_8") (pintype "passive"))
      (node (ref "U7") (pin "6") (pinfunction "VCC_6") (pintype "passive"))
      (node (ref "U8") (pin "8") (pinfunction "V+_8") (pintype "passive"))
    )
    (net (code "64") (name "GND") (class "Default")
      (node (ref "C1") (pin "2") (pinfunction "2_2") (pintype "passive"))
      (node (ref "C10") (pin "1") (pinfunction "1_1") (pintype "passive"))
      (node (ref "C14") (pin "1") (pinfunction "1_1") (pintype "passive"))
      (node (ref "C15") (pin "1") (pinfunction "1_1") (pintype "passive"))
      (node (ref "C17") (pin "1") (pinfunction "1_1") (pintype "passive"))
      (node (ref "C18") (pin "1") (pinfunction "1_1") (pintype "passive"))
      (node (ref "C19") (pin "1") (pinfunction "1_1") (pintype "passive"))
      (node (ref "C2") (pin "2") (pinfunction "2_2") (pintype "passive"))
      (node (ref "C20") (pin "1") (pinfunction "1_1") (pintype "passive"))
      (node (ref "C21") (pin "1") (pinfunction "1_1") (pintype "passive"))
      (node (ref "C22") (pin "2") (pinfunction "2_2") (pintype "passive"))
      (node (ref "C23") (pin "2") (pinfunction "2_2") (pintype "passive"))
      (node (ref "C24") (pin "1") (pinfunction "1_1") (pintype "passive"))
      (node (ref "C27") (pin "2") (pinfunction "2_2") (pintype "passive"))
      (node (ref "C3") (pin "2") (pinfunction "2_2") (pintype "passive"))
      (node (ref "C4") (pin "2") (pinfunction "2_2") (pintype "passive"))
      (node (ref "C5") (pin "2") (pinfunction "2_2") (pintype "passive"))
      (node (ref "C6") (pin "1") (pinfunction "1_1") (pintype "passive"))
      (node (ref "C9") (pin "2") (pinfunction "2_2") (pintype "passive"))
      (node (ref "J1") (pin "1") (pinfunction "GND_1") (pintype "passive"))
      (node (ref "J1") (pin "34") (pinfunction "GND_34") (pintype "passive"))
      (node (ref "J1") (pin "35") (pinfunction "GND_35") (pintype "passive"))
      (node (ref "J1") (pin "36") (pinfunction "~{CD1}_36") (pintype "passive"))
      (node (ref "J1") (pin "57") (pinfunction "~{VS2}_57") (pintype "passive"))
      (node (ref "J1") (pin "67") (pinfunction "~{CD2}_67") (pintype "passive"))
      (node (ref "J1") (pin "68") (pinfunction "GND_68") (pintype "passive"))
      (node (ref "J2") (pin "1") (pintype "passive"))
      (node (ref "J2") (pin "2") (pintype "passive"))
      (node (ref "Q1") (pin "2") (pinfunction "E_2") (pintype "passive"))
      (node (ref "Q2") (pin "2") (pinfunction "E_2") (pintype "passive"))
      (node (ref "R12") (pin "1") (pinfunction "1_1") (pintype "passive"))
      (node (ref "R2") (pin "1") (pinfunction "1_1") (pintype "passive"))
      (node (ref "R21") (pin "1") (pinfunction "1_1") (pintype "passive"))
      (node (ref "R26") (pin "1") (pinfunction "1_1") (pintype "passive"))
      (node (ref "R30") (pin "1") (pinfunction "1_1") (pintype "passive"))
      (node (ref "R31") (pin "1") (pinfunction "1_1") (pintype "passive"))
      (node (ref "RP1") (pin "1") (pintype "passive"))
      (node (ref "U1") (pin "7") (pinfunction "GND_7") (pintype "passive"))
      (node (ref "U2") (pin "15") (pinfunction "VSS_15") (pintype "passive"))
      (node (ref "U2") (pin "20") (pinfunction "VSS_20") (pintype "passive"))
      (node (ref "U2") (pin "32") (pinfunction "VSS_32") (pintype "passive"))
      (node (ref "U2") (pin "44") (pinfunction "VSS_44") (pintype "passive"))
      (node (ref "U2") (pin "5") (pinfunction "VSS_5") (pintype "passive"))
      (node (ref "U2") (pin "68") (pinfunction "VSS_68") (pintype "passive"))
      (node (ref "U2") (pin "77") (pinfunction "VSS_77") (pintype "passive"))
      (node (ref "U2") (pin "88") (pinfunction "VSS_88") (pintype "passive"))
      (node (ref "U3") (pin "5") (pinfunction "VSS_5") (pintype "passive"))
      (node (ref "U3") (pin "6") (pinfunction "ORG_6") (pintype "passive"))
      (node (ref "U4") (pin "11") (pinfunction "5A_11") (pintype "passive"))
      (node (ref "U4") (pin "13") (pinfunction "6A_13") (pintype "passive"))
      (node (ref "U4") (pin "3") (pinfunction "2A_3") (pintype "passive"))
      (node (ref "U4") (pin "7") (pinfunction "GND_7") (pintype "passive"))
      (node (ref "U5") (pin "1") (pinfunction "VSS_1") (pintype "passive"))
      (node (ref "U5") (pin "14") (pinfunction "VSS_14") (pintype "passive"))
      (node (ref "U5") (pin "16") (pinfunction "VSS_16") (pintype "passive"))
      (node (ref "U6") (pin "3") (pinfunction "GND_3") (pintype "passive"))
      (node (ref "U7") (pin "7") (pinfunction "GND_7") (pintype "passive"))
      (node (ref "U8") (pin "4") (pinfunction "V-_4") (pintype "passive"))
      (node (ref "UX1") (pin "2") (pinfunction "GND_2") (pintype "passive"))
    )
    (net (code "65") (name "Net-(C2-Pad1)") (class "Default")
      (node (ref "C2") (pin "1") (pinfunction "1_1") (pintype "passive"))
      (node (ref "R1") (pin "1") (pinfunction "1_1") (pintype "passive"))
      (node (ref "R8") (pin "2") (pinfunction "2_2") (pintype "passive"))
    )
    (net (code "66") (name "Net-(C7-Pad1)") (class "Default")
      (node (ref "C7") (pin "1") (pinfunction "1_1") (pintype "passive"))
      (node (ref "R5") (pin "2") (pinfunction "2_2") (pintype "passive"))
    )
    (net (code "67") (name "Net-(C7-Pad2)") (class "Default")
      (node (ref "C7") (pin "2") (pinfunction "2_2") (pintype "passive"))
      (node (ref "J2") (pin "6") (pintype "passive"))
    )
    (net (code "68") (name "Net-(C8-Pad2)") (class "Default")
      (node (ref "C8") (pin "2") (pinfunction "2_2") (pintype "passive"))
      (node (ref "R18") (pin "2") (pinfunction "2_2") (pintype "passive"))
      (node (ref "R19") (pin "2") (pinfunction "2_2") (pintype "passive"))
    )
    (net (code "69") (name "Net-(C9-Pad1)") (class "Default")
      (node (ref "C9") (pin "1") (pinfunction "1_1") (pintype "passive"))
      (node (ref "R22") (pin "1") (pinfunction "1_1") (pintype "passive"))
    )
    (net (code "70") (name "Net-(C10-Pad2)") (class "Default")
      (node (ref "C10") (pin "2") (pinfunction "2_2") (pintype "passive"))
      (node (ref "R23") (pin "1") (pinfunction "1_1") (pintype "passive"))
    )
    (net (code "71") (name "Net-(C11-Pad1)") (class "Default")
      (node (ref "C11") (pin "1") (pinfunction "1_1") (pintype "passive"))
      (node (ref "RP1") (pin "3") (pintype "passive"))
    )
    (net (code "72") (name "Net-(C11-Pad2)") (class "Default")
      (node (ref "C11") (pin "2") (pinfunction "2_2") (pintype "passive"))
      (node (ref "R29") (pin "1") (pinfunction "1_1") (pintype "passive"))
      (node (ref "R30") (pin "2") (pinfunction "2_2") (pintype "passive"))
      (node (ref "U8") (pin "3") (pintype "passive"))
    )
    (net (code "73") (name "Net-(C12-Pad1)") (class "Default")
      (node (ref "C12") (pin "1") (pinfunction "1_1") (pintype "passive"))
      (node (ref "RP1") (pin "2") (pintype "passive"))
    )
    (net (code "74") (name "Net-(C12-Pad2)") (class "Default")
      (node (ref "C12") (pin "2") (pinfunction "2_2") (pintype "passive"))
      (node (ref "R31") (pin "2") (pinfunction "2_2") (pintype "passive"))
      (node (ref "R33") (pin "1") (pinfunction "1_1") (pintype "passive"))
      (node (ref "U8") (pin "5") (pintype "passive"))
    )
    (net (code "75") (name "Net-(C13-Pad1)") (class "Default")
      (node (ref "C13") (pin "1") (pinfunction "1_1") (pintype "passive"))
      (node (ref "C26") (pin "1") (pinfunction "1_1") (pintype "passive"))
      (node (ref "R25") (pin "2") (pinfunction "2_2") (pintype "passive"))
      (node (ref "U8") (pin "7") (pintype "passive"))
    )
    (net (code "76") (name "Net-(C13-Pad2)") (class "Default")
      (node (ref "C13") (pin "2") (pinfunction "2_2") (pintype "passive"))
      (node (ref "R27") (pin "2") (pinfunction "2_2") (pintype "passive"))
      (node (ref "R28") (pin "2") (pinfunction "2_2") (pintype "passive"))
    )
    (net (code "77") (name "Net-(C16-Pad1)") (class "Default")
      (node (ref "C16") (pin "1") (pinfunction "1_1") (pintype "passive"))
      (node (ref "R11") (pin "2") (pinfunction "2_2") (pintype "passive"))
    )
    (net (code "78") (name "Net-(C16-Pad2)") (class "Default")
      (node (ref "C16") (pin "2") (pinfunction "2_2") (pintype "passive"))
      (node (ref "J2") (pin "5") (pintype "passive"))
    )
    (net (code "79") (name "Net-(C23-Pad1)") (class "Default")
      (node (ref "C23") (pin "1") (pinfunction "1_1") (pintype "passive"))
      (node (ref "R14") (pin "2") (pinfunction "2_2") (pintype "passive"))
    )
    (net (code "80") (name "Net-(C25-Pad1)") (class "Default")
      (node (ref "C25") (pin "1") (pinfunction "1_1") (pintype "passive"))
      (node (ref "C8") (pin "1") (pinfunction "1_1") (pintype "passive"))
      (node (ref "R24") (pin "2") (pinfunction "2_2") (pintype "passive"))
      (node (ref "U8") (pin "1") (pintype "passive"))
    )
    (net (code "81") (name "Net-(C25-Pad2)") (class "Default")
      (node (ref "C25") (pin "2") (pinfunction "2_2") (pintype "passive"))
      (node (ref "R22") (pin "2") (pinfunction "2_2") (pintype "passive"))
      (node (ref "R24") (pin "1") (pinfunction "1_1") (pintype "passive"))
      (node (ref "U8") (pin "2") (pintype "passive"))
    )
    (net (code "82") (name "Net-(C26-Pad2)") (class "Default")
      (node (ref "C26") (pin "2") (pinfunction "2_2") (pintype "passive"))
      (node (ref "R23") (pin "2") (pinfunction "2_2") (pintype "passive"))
      (node (ref "R25") (pin "1") (pinfunction "1_1") (pintype "passive"))
      (node (ref "U8") (pin "6") (pintype "passive"))
    )
    (net (code "83") (name "Net-(J1-WP{slash}~{IOIS16})") (class "Default")
      (node (ref "J1") (pin "33") (pinfunction "WP/~{IOIS16}_33") (pintype "passive"))
      (node (ref "U2") (pin "10") (pinfunction "PC_WP/~{IOIS16}/~{IOCS16}_10") (pintype "passive"))
    )
    (net (code "84") (name "Net-(Q1-B)") (class "Default")
      (node (ref "Q1") (pin "1") (pinfunction "B_1") (pintype "passive"))
      (node (ref "R10") (pin "1") (pinfunction "1_1") (pintype "passive"))
    )
    (net (code "85") (name "Net-(Q1-C)") (class "Default")
      (node (ref "J2") (pin "4") (pintype "passive"))
      (node (ref "Q1") (pin "3") (pinfunction "C_3") (pintype "passive"))
      (node (ref "R18") (pin "1") (pinfunction "1_1") (pintype "passive"))
      (node (ref "R19") (pin "1") (pinfunction "1_1") (pintype "passive"))
      (node (ref "R21") (pin "2") (pinfunction "2_2") (pintype "passive"))
    )
    (net (code "86") (name "Net-(Q2-B)") (class "Default")
      (node (ref "Q2") (pin "1") (pinfunction "B_1") (pintype "passive"))
      (node (ref "R3") (pin "1") (pinfunction "1_1") (pintype "passive"))
    )
    (net (code "87") (name "Net-(Q2-C)") (class "Default")
      (node (ref "J2") (pin "3") (pintype "passive"))
      (node (ref "Q2") (pin "3") (pinfunction "C_3") (pintype "passive"))
      (node (ref "R26") (pin "2") (pinfunction "2_2") (pintype "passive"))
      (node (ref "R27") (pin "1") (pinfunction "1_1") (pintype "passive"))
      (node (ref "R28") (pin "1") (pinfunction "1_1") (pintype "passive"))
    )
    (net (code "88") (name "Net-(R10-Pad2)") (class "Default")
      (node (ref "R10") (pin "2") (pinfunction "2_2") (pintype "passive"))
      (node (ref "R2") (pin "2") (pinfunction "2_2") (pintype "passive"))
      (node (ref "R3") (pin "2") (pinfunction "2_2") (pintype "passive"))
      (node (ref "R9") (pin "2") (pinfunction "2_2") (pintype "passive"))
    )
    (net (code "89") (name "Net-(U1-1D)") (class "Default")
      (node (ref "U1") (pin "2") (pinfunction "1D_2") (pintype "passive"))
      (node (ref "U1") (pin "6") (pinfunction "1~{Q}_6") (pintype "passive"))
    )
    (net (code "90") (name "Net-(U1-1Q)") (class "Default")
      (node (ref "U1") (pin "5") (pinfunction "1Q_5") (pintype "passive"))
      (node (ref "U2") (pin "58") (pinfunction "PC_MCLK_IN_58") (pintype "passive"))
    )
    (net (code "91") (name "Net-(U1-2CLK)") (class "Default")
      (node (ref "U1") (pin "11") (pinfunction "2CLK_11") (pintype "passive"))
      (node (ref "U4") (pin "2") (pinfunction "1Y_2") (pintype "passive"))
    )
    (net (code "92") (name "Net-(U1-2Q)") (class "Default")
      (node (ref "U1") (pin "9") (pinfunction "2Q_9") (pintype "passive"))
      (node (ref "U5") (pin "11") (pinfunction "~{IC}_11") (pintype "passive"))
    )
    (net (code "93") (name "Net-(U1-2~{CLR})") (class "Default")
      (node (ref "U1") (pin "13") (pinfunction "2~{CLR}_13") (pintype "passive"))
      (node (ref "U2") (pin "11") (pinfunction "~{ATA}_HRESET_11") (pintype "passive"))
    )
    (net (code "94") (name "Net-(U2-EE_CS)") (class "Default")
      (node (ref "U2") (pin "52") (pinfunction "EE_CS_52") (pintype "passive"))
      (node (ref "U3") (pin "1") (pinfunction "S_1") (pintype "passive"))
    )
    (net (code "95") (name "Net-(U2-EE_D0)") (class "Default")
      (node (ref "U2") (pin "53") (pinfunction "EE_D0_53") (pintype "passive"))
      (node (ref "U3") (pin "3") (pinfunction "D_3") (pintype "passive"))
    )
    (net (code "96") (name "Net-(U2-EE_D1)") (class "Default")
      (node (ref "U2") (pin "54") (pinfunction "EE_D1_54") (pintype "passive"))
      (node (ref "U3") (pin "4") (pinfunction "Q_4") (pintype "passive"))
    )
    (net (code "97") (name "Net-(U2-EE_MASTER)") (class "Default")
      (node (ref "R7") (pin "1") (pinfunction "1_1") (pintype "passive"))
      (node (ref "U2") (pin "51") (pinfunction "EE_MASTER_51") (pintype "passive"))
    )
    (net (code "98") (name "Net-(U2-EE_SK)") (class "Default")
      (node (ref "U2") (pin "50") (pinfunction "EE_SK_50") (pintype "passive"))
      (node (ref "U3") (pin "2") (pinfunction "C_2") (pintype "passive"))
    )
    (net (code "99") (name "Net-(U2-EXTP_AUDIO)") (class "Default")
      (node (ref "R4") (pin "1") (pinfunction "1_1") (pintype "passive"))
      (node (ref "U2") (pin "60") (pinfunction "EXTP_AUDIO_60") (pintype "passive"))
    )
    (net (code "100") (name "Net-(U2-~{POR})") (class "Default")
      (node (ref "C19") (pin "2") (pinfunction "2_2") (pintype "passive"))
      (node (ref "U2") (pin "56") (pinfunction "~{POR}_56") (pintype "passive"))
    )
    (net (code "101") (name "Net-(U4-3A)") (class "Default")
      (node (ref "R1") (pin "2") (pinfunction "2_2") (pintype "passive"))
      (node (ref "U4") (pin "5") (pinfunction "3A_5") (pintype "passive"))
    )
    (net (code "102") (name "Net-(U4-3Y)") (class "Default")
      (node (ref "R9") (pin "1") (pinfunction "1_1") (pintype "passive"))
      (node (ref "U4") (pin "6") (pinfunction "3Y_6") (pintype "passive"))
    )
    (net (code "103") (name "Net-(U6-L.OUT)") (class "Default")
      (node (ref "RP1") (pin "4") (pintype "passive"))
      (node (ref "U6") (pin "4") (pinfunction "L.OUT_4") (pintype "passive"))
    )
    (net (code "104") (name "Net-(U6-R.OUT)") (class "Default")
      (node (ref "RP1") (pin "5") (pintype "passive"))
      (node (ref "U6") (pin "1") (pinfunction "R.OUT_1") (pintype "passive"))
    )
    (net (code "105") (name "Net-(U6-REF)") (class "Default")
      (node (ref "C5") (pin "1") (pinfunction "1_1") (pintype "passive"))
      (node (ref "U6") (pin "2") (pinfunction "REF_2") (pintype "passive"))
    )
    (net (code "106") (name "Net-(U7-Bypass)") (class "Default")
      (node (ref "C24") (pin "2") (pinfunction "2_2") (pintype "passive"))
      (node (ref "U7") (pin "2") (pinfunction "Bypass_2") (pintype "passive"))
    )
    (net (code "107") (name "Net-(U7-INN)") (class "Default")
      (node (ref "R14") (pin "1") (pinfunction "1_1") (pintype "passive"))
      (node (ref "U7") (pin "4") (pinfunction "INN_4") (pintype "passive"))
    )
    (net (code "108") (name "Net-(U7-INP)") (class "Default")
      (node (ref "R11") (pin "1") (pinfunction "1_1") (pintype "passive"))
      (node (ref "R5") (pin "1") (pinfunction "1_1") (pintype "passive"))
      (node (ref "U7") (pin "3") (pinfunction "INP_3") (pintype "passive"))
    )
    (net (code "109") (name "Net-(U7-VoN)") (class "Default")
      (node (ref "LS1") (pin "2") (pinfunction "2_2") (pintype "passive"))
      (node (ref "LS1") (pin "2A") (pinfunction "2A_2A") (pintype "passive"))
      (node (ref "U7") (pin "5") (pinfunction "VoN_5") (pintype "passive"))
    )
    (net (code "110") (name "Net-(U7-VoP)") (class "Default")
      (node (ref "LS1") (pin "1") (pinfunction "1_1") (pintype "passive"))
      (node (ref "LS1") (pin "1A") (pinfunction "1A_1A") (pintype "passive"))
      (node (ref "U7") (pin "8") (pinfunction "VoP_8") (pintype "passive"))
    )
    (net (code "111") (name "Net-(UX1-EN)") (class "Default")
      (node (ref "R12") (pin "2") (pinfunction "2_2") (pintype "passive"))
      (node (ref "UX1") (pin "1") (pinfunction "EN_1") (pintype "passive"))
    )
    (net (code "112") (name "unconnected-(J1-A11-Pad10)") (class "Default")
      (node (ref "J1") (pin "10") (pinfunction "A11_10") (pintype "passive+no_connect"))
    )
    (net (code "113") (name "unconnected-(J1-A12-Pad21)") (class "Default")
      (node (ref "J1") (pin "21") (pinfunction "A12_21") (pintype "passive+no_connect"))
    )
    (net (code "114") (name "unconnected-(J1-A13-Pad13)") (class "Default")
      (node (ref "J1") (pin "13") (pinfunction "A13_13") (pintype "passive+no_connect"))
    )
    (net (code "115") (name "unconnected-(J1-A14-Pad14)") (class "Default")
      (node (ref "J1") (pin "14") (pinfunction "A14_14") (pintype "passive+no_connect"))
    )
    (net (code "116") (name "unconnected-(J1-A15-Pad20)") (class "Default")
      (node (ref "J1") (pin "20") (pinfunction "A15_20") (pintype "passive+no_connect"))
    )
    (net (code "117") (name "unconnected-(J1-A16-Pad19)") (class "Default")
      (node (ref "J1") (pin "19") (pinfunction "A16_19") (pintype "passive+no_connect"))
    )
    (net (code "118") (name "unconnected-(J1-A17-Pad46)") (class "Default")
      (node (ref "J1") (pin "46") (pinfunction "A17_46") (pintype "passive+no_connect"))
    )
    (net (code "119") (name "unconnected-(J1-A18-Pad47)") (class "Default")
      (node (ref "J1") (pin "47") (pinfunction "A18_47") (pintype "passive+no_connect"))
    )
    (net (code "120") (name "unconnected-(J1-A19-Pad48)") (class "Default")
      (node (ref "J1") (pin "48") (pinfunction "A19_48") (pintype "passive+no_connect"))
    )
    (net (code "121") (name "unconnected-(J1-A20-Pad49)") (class "Default")
      (node (ref "J1") (pin "49") (pinfunction "A20_49") (pintype "passive+no_connect"))
    )
    (net (code "122") (name "unconnected-(J1-A21-Pad50)") (class "Default")
      (node (ref "J1") (pin "50") (pinfunction "A21_50") (pintype "passive+no_connect"))
    )
    (net (code "123") (name "unconnected-(J1-A22-Pad53)") (class "Default")
      (node (ref "J1") (pin "53") (pinfunction "A22_53") (pintype "passive+no_connect"))
    )
    (net (code "124") (name "unconnected-(J1-A23-Pad54)") (class "Default")
      (node (ref "J1") (pin "54") (pinfunction "A23_54") (pintype "passive+no_connect"))
    )
    (net (code "125") (name "unconnected-(J1-A24-Pad55)") (class "Default")
      (node (ref "J1") (pin "55") (pinfunction "A24_55") (pintype "passive+no_connect"))
    )
    (net (code "126") (name "unconnected-(J1-A25-Pad56)") (class "Default")
      (node (ref "J1") (pin "56") (pinfunction "A25_56") (pintype "passive+no_connect"))
    )
    (net (code "127") (name "unconnected-(J1-VPP1-Pad18)") (class "Default")
      (node (ref "J1") (pin "18") (pinfunction "VPP1_18") (pintype "passive+no_connect"))
    )
    (net (code "128") (name "unconnected-(J1-VPP2-Pad52)") (class "Default")
      (node (ref "J1") (pin "52") (pinfunction "VPP2_52") (pintype "passive+no_connect"))
    )
    (net (code "129") (name "unconnected-(J1-~{BVD2}{slash}SPKR-Pad62)") (class "Default")
      (node (ref "J1") (pin "62") (pinfunction "~{BVD2}/SPKR_62") (pintype "passive+no_connect"))
    )
    (net (code "130") (name "unconnected-(J1-~{VS1}-Pad43)") (class "Default")
      (node (ref "J1") (pin "43") (pinfunction "~{VS1}_43") (pintype "passive+no_connect"))
    )
    (net (code "131") (name "unconnected-(U1-2~{Q}-Pad8)") (class "Default")
      (node (ref "U1") (pin "8") (pinfunction "2~{Q}_8") (pintype "passive+no_connect"))
    )
    (net (code "132") (name "unconnected-(U2-ATA_DATA8{slash}RES1-Pad13)") (class "Default")
      (node (ref "U2") (pin "13") (pinfunction "ATA_DATA8/RES1_13") (pintype "passive+no_connect"))
    )
    (net (code "133") (name "unconnected-(U2-ATA_DATA9{slash}PACK_IN-Pad17)") (class "Default")
      (node (ref "U2") (pin "17") (pinfunction "ATA_DATA9/PACK_IN_17") (pintype "passive+no_connect"))
    )
    (net (code "134") (name "unconnected-(U2-ATA_DATA10-Pad19)") (class "Default")
      (node (ref "U2") (pin "19") (pinfunction "ATA_DATA10_19") (pintype "passive+no_connect"))
    )
    (net (code "135") (name "unconnected-(U2-ATA_DATA11-Pad22)") (class "Default")
      (node (ref "U2") (pin "22") (pinfunction "ATA_DATA11_22") (pintype "passive+no_connect"))
    )
    (net (code "136") (name "unconnected-(U2-ATA_DATA12-Pad25)") (class "Default")
      (node (ref "U2") (pin "25") (pinfunction "ATA_DATA12_25") (pintype "passive+no_connect"))
    )
    (net (code "137") (name "unconnected-(U2-ATA_DATA13-Pad27)") (class "Default")
      (node (ref "U2") (pin "27") (pinfunction "ATA_DATA13_27") (pintype "passive+no_connect"))
    )
    (net (code "138") (name "unconnected-(U2-ATA_DATA14-Pad29)") (class "Default")
      (node (ref "U2") (pin "29") (pinfunction "ATA_DATA14_29") (pintype "passive+no_connect"))
    )
    (net (code "139") (name "unconnected-(U2-ATA_DATA15-Pad31)") (class "Default")
      (node (ref "U2") (pin "31") (pinfunction "ATA_DATA15_31") (pintype "passive+no_connect"))
    )
    (net (code "140") (name "unconnected-(U2-ATA_HA2-Pad41)") (class "Default")
      (node (ref "U2") (pin "41") (pinfunction "ATA_HA2_41") (pintype "passive+no_connect"))
    )
    (net (code "141") (name "unconnected-(U2-ATA_HCS1-Pad43)") (class "Default")
      (node (ref "U2") (pin "43") (pinfunction "ATA_HCS1_43") (pintype "passive+no_connect"))
    )
    (net (code "142") (name "unconnected-(U2-ATA_IOCHRDY-Pad35)") (class "Default")
      (node (ref "U2") (pin "35") (pinfunction "ATA_IOCHRDY_35") (pintype "passive+no_connect"))
    )
    (net (code "143") (name "unconnected-(U2-EXTP_APWDN-Pad59)") (class "Default")
      (node (ref "U2") (pin "59") (pinfunction "EXTP_APWDN_59") (pintype "passive+no_connect"))
    )
    (net (code "144") (name "unconnected-(U2-EXTP_STSCHG{slash}RES2-Pad61)") (class "Default")
      (node (ref "U2") (pin "61") (pinfunction "EXTP_STSCHG/RES2_61") (pintype "passive+no_connect"))
    )
    (net (code "145") (name "unconnected-(U2-V_PINT-Pad57)") (class "Default")
      (node (ref "U2") (pin "57") (pinfunction "V_PINT_57") (pintype "passive+no_connect"))
    )
    (net (code "146") (name "unconnected-(U2-~{ATA}_DACK{slash}BVD2-Pad47)") (class "Default")
      (node (ref "U2") (pin "47") (pinfunction "~{ATA}_DACK/BVD2_47") (pintype "passive+no_connect"))
    )
    (net (code "147") (name "unconnected-(U2-~{ATA}_DREQ{slash}BVD1-Pad48)") (class "Default")
      (node (ref "U2") (pin "48") (pinfunction "~{ATA}_DREQ/BVD1_48") (pintype "passive+no_connect"))
    )
    (net (code "148") (name "unconnected-(U2-~{ATA}_IOCS16-Pad37)") (class "Default")
      (node (ref "U2") (pin "37") (pinfunction "~{ATA}_IOCS16_37") (pintype "passive+no_connect"))
    )
    (net (code "149") (name "unconnected-(U2-~{ATA}_MRD-Pad49)") (class "Default")
      (node (ref "U2") (pin "49") (pinfunction "~{ATA}_MRD_49") (pintype "passive+no_connect"))
    )
    (net (code "150") (name "unconnected-(U2-~{ATA}_MWR-Pad55)") (class "Default")
      (node (ref "U2") (pin "55") (pinfunction "~{ATA}_MWR_55") (pintype "passive+no_connect"))
    )
    (net (code "151") (name "unconnected-(U2-~{ATA}_PDASP{slash}EXTP_WP-Pad46)") (class "Default")
      (node (ref "U2") (pin "46") (pinfunction "~{ATA}_PDASP/EXTP_WP_46") (pintype "passive+no_connect"))
    )
    (net (code "152") (name "unconnected-(U2-~{ATA}_PDIAG{slash}ATA_BHE{slash}RING_IN-Pad45)") (class "Default")
      (node (ref "U2") (pin "45") (pinfunction "~{ATA}_PDIAG/ATA_BHE/RING_IN_45") (pintype "passive+no_connect"))
    )
    (net (code "153") (name "unconnected-(U3-DU-Pad7)") (class "Default")
      (node (ref "U3") (pin "7") (pinfunction "DU_7") (pintype "passive+no_connect"))
    )
    (net (code "154") (name "unconnected-(U4-1A-Pad1)") (class "Default")
      (node (ref "U4") (pin "1") (pinfunction "1A_1") (pintype "passive"))
    )
    (net (code "155") (name "unconnected-(U4-2Y-Pad4)") (class "Default")
      (node (ref "U4") (pin "4") (pinfunction "2Y_4") (pintype "passive+no_connect"))
    )
    (net (code "156") (name "unconnected-(U4-5Y-Pad10)") (class "Default")
      (node (ref "U4") (pin "10") (pinfunction "5Y_10") (pintype "passive+no_connect"))
    )
    (net (code "157") (name "unconnected-(U4-6Y-Pad12)") (class "Default")
      (node (ref "U4") (pin "12") (pinfunction "6Y_12") (pintype "passive+no_connect"))
    )
    (net (code "158") (name "unconnected-(U5-NC-Pad10)") (class "Default")
      (node (ref "U5") (pin "10") (pinfunction "NC_10") (pintype "passive+no_connect"))
    )
    (net (code "159") (name "unconnected-(U5-NC-Pad13)") (class "Default")
      (node (ref "U5") (pin "13") (pinfunction "NC_13") (pintype "passive+no_connect"))
    )
    (net (code "160") (name "unconnected-(U5-WCO-Pad25)") (class "Default")
      (node (ref "U5") (pin "25") (pinfunction "WCO_25") (pintype "passive"))
    )
  )
)
